# power.net
KiCad netlist of a schematic drawn in Altium Designer
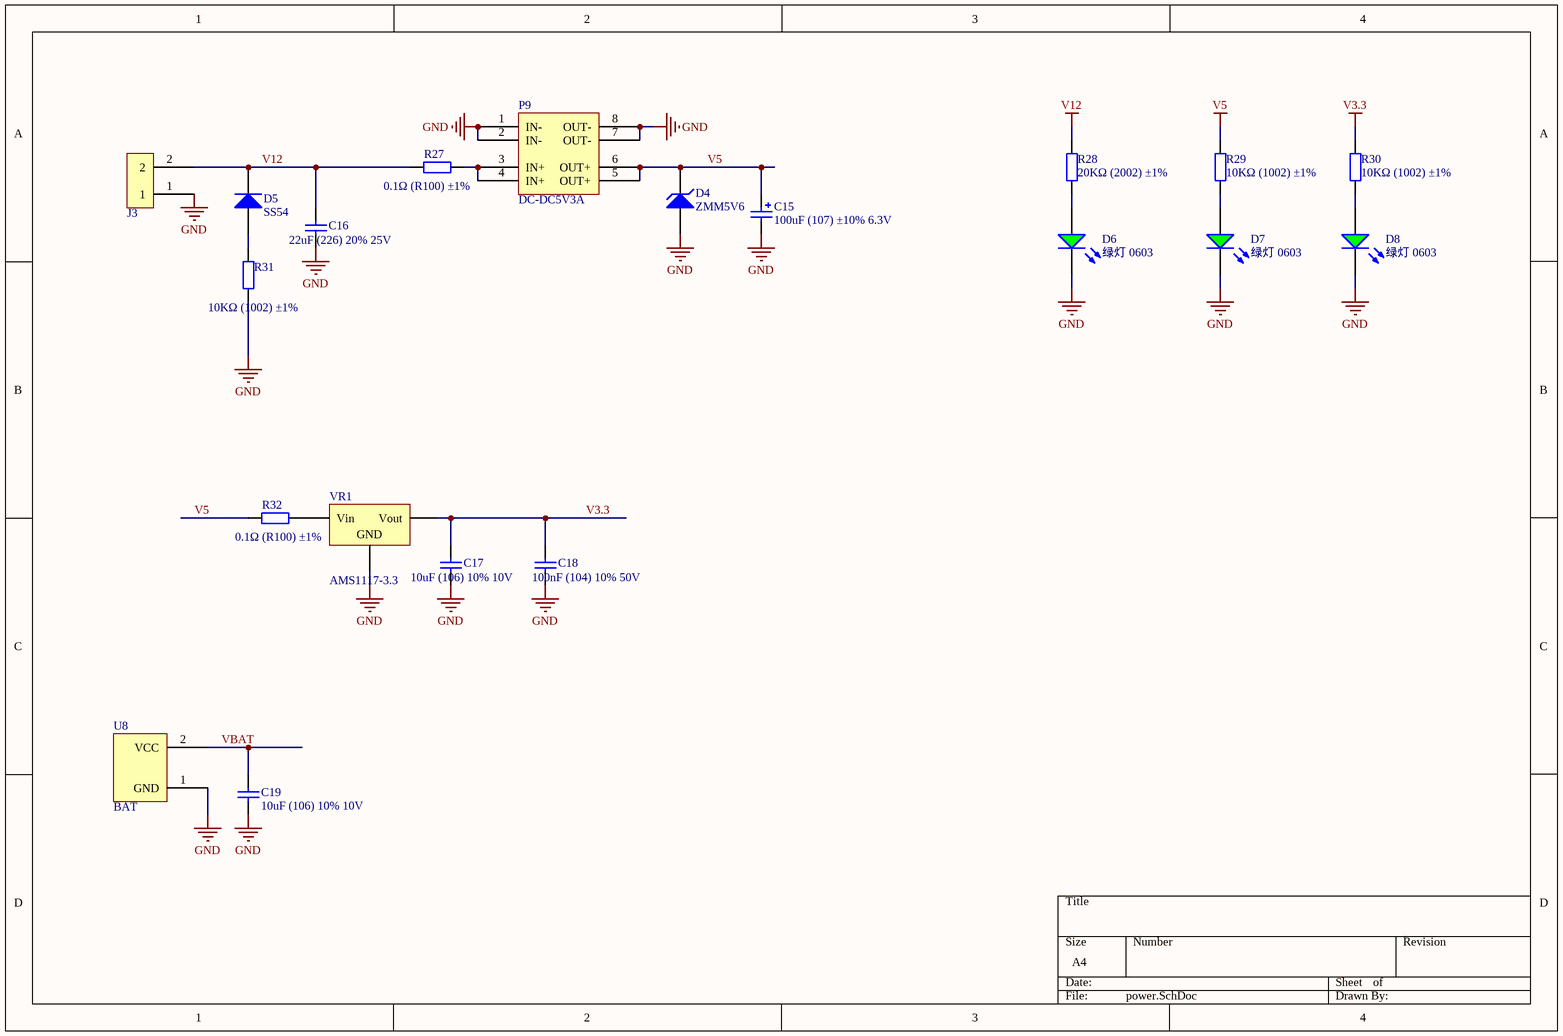
[diagram p0: power.SchDoc]

(export (version "E")
  (design (tool "Eeschema 10.0.6"))
  (components
    (comp (ref "C15")
      (value "100uF (107) ±10% 6.3V")
      (footprint "CASE-B_3528")
      (description "钽电容")
      (libsource (lib "Miscellaneous Devices LC") (part "3528 100uF (107) 10% 6.3V"))
    )
    (comp (ref "C16")
      (value "22uF (226) 20% 25V")
      (footprint "0805_C")
      (description "贴片电容")
      (libsource (lib "Miscellaneous Devices LC") (part "0805 22uF (226) 20% 25V"))
    )
    (comp (ref "C17")
      (value "10uF (106) 10% 10V")
      (footprint "0603_C")
      (description "贴片电容")
      (libsource (lib "Miscellaneous Devices LC") (part "0603 10uF (106) 10% 10V"))
    )
    (comp (ref "C18")
      (value "100nF (104) 10% 50V")
      (footprint "0603_C")
      (description "贴片电容")
      (libsource (lib "Miscellaneous Devices LC") (part "0603 100nF (104) 10% 50V"))
    )
    (comp (ref "C19")
      (value "10uF (106) 10% 10V")
      (footprint "0603_C")
      (description "贴片电容")
      (libsource (lib "Miscellaneous Devices LC") (part "0603 10uF (106) 10% 10V"))
    )
    (comp (ref "D4")
      (value "ZMM5V6")
      (footprint "LL-34")
      (description "稳压二极管")
      (libsource (lib "Miscellaneous Devices LC") (part "LL-34 ZMM5V6"))
    )
    (comp (ref "D5")
      (value "SS54")
      (footprint "SMA(DO-214AC)_S1")
      (description "二极管")
      (libsource (lib "Miscellaneous Devices LC") (part "SMA(DO-214AC) SS54"))
    )
    (comp (ref "D6")
      (value "绿灯 0603")
      (footprint "0603_LED_S1")
      (description "发光二极管")
      (libsource (lib "Miscellaneous Devices LC") (part "0603 绿灯"))
    )
    (comp (ref "D7")
      (value "绿灯 0603")
      (footprint "0603_LED_S1")
      (description "发光二极管")
      (libsource (lib "Miscellaneous Devices LC") (part "0603 绿灯"))
    )
    (comp (ref "D8")
      (value "绿灯 0603")
      (footprint "0603_LED_S1")
      (description "发光二极管")
      (libsource (lib "Miscellaneous Devices LC") (part "0603 绿灯"))
    )
    (comp (ref "J3") (value "XK7.62-2P") (footprint "XK7.62-2P") (libsource (lib "CHK-I") (part "XK7.62-2P")))
    (comp (ref "P9") (value "DC-DC5V3A") (footprint "DC-DC3A") (libsource (lib "CHK-I") (part "DC-DC3A")))
    (comp (ref "R27")
      (value "0.1Ω (R100) ±1%")
      (footprint "1206_R")
      (description "贴片电阻")
      (libsource (lib "Miscellaneous Devices LC") (part "1206 0.1Ω (R100) 1%"))
    )
    (comp (ref "R28")
      (value "20KΩ (2002) ±1%")
      (footprint "0603_R")
      (description "贴片电阻")
      (libsource (lib "Miscellaneous Devices LC") (part "0603 20KΩ (2002) 1%"))
    )
    (comp (ref "R29")
      (value "10KΩ (1002) ±1%")
      (footprint "0603_R")
      (description "贴片电阻")
      (libsource (lib "Miscellaneous Devices LC") (part "0603 10KΩ (1002) 1%"))
    )
    (comp (ref "R30")
      (value "10KΩ (1002) ±1%")
      (footprint "0603_R")
      (description "贴片电阻")
      (libsource (lib "Miscellaneous Devices LC") (part "0603 10KΩ (1002) 1%"))
    )
    (comp (ref "R31")
      (value "10KΩ (1002) ±1%")
      (footprint "0805_R")
      (description "贴片电阻")
      (libsource (lib "Miscellaneous Devices LC") (part "0805 10KΩ (1002) 1%"))
    )
    (comp (ref "R32")
      (value "0.1Ω (R100) ±1%")
      (footprint "1206_R")
      (description "贴片电阻")
      (libsource (lib "Miscellaneous Devices LC") (part "1206 0.1Ω (R100) 1%"))
    )
    (comp (ref "U8") (value "BAT") (footprint "BAT2032") (libsource (lib "CHK-I") (part "BAT2032")))
    (comp (ref "VR1")
      (value "AMS1117-3.3")
      (footprint "SOT-223")
      (description "低压差线性稳压(LDO)")
      (libsource (lib "Miscellaneous Devices LC") (part "SOT-223 AMS1117-3.3"))
    )
  )
  (nets
    (net (code "1") (name "/VBAT") (class "Default")
      (node (ref "C19") (pin "2") (pinfunction "2_2") (pintype "passive"))
      (node (ref "U8") (pin "2") (pinfunction "VCC_2") (pintype "passive"))
    )
    (net (code "2") (name "GND") (class "Default")
      (node (ref "C15") (pin "2") (pinfunction "2_2") (pintype "passive"))
      (node (ref "C16") (pin "1") (pinfunction "1_1") (pintype "passive"))
      (node (ref "C17") (pin "1") (pinfunction "1_1") (pintype "passive"))
      (node (ref "C18") (pin "1") (pinfunction "1_1") (pintype "passive"))
      (node (ref "C19") (pin "1") (pinfunction "1_1") (pintype "passive"))
      (node (ref "D4") (pin "1") (pinfunction "A_1") (pintype "passive"))
      (node (ref "D6") (pin "K") (pinfunction "K_K") (pintype "passive"))
      (node (ref "D7") (pin "K") (pinfunction "K_K") (pintype "passive"))
      (node (ref "D8") (pin "K") (pinfunction "K_K") (pintype "passive"))
      (node (ref "J3") (pin "1") (pinfunction "1_1") (pintype "passive"))
      (node (ref "P9") (pin "1") (pinfunction "IN-_1") (pintype "passive"))
      (node (ref "P9") (pin "2") (pinfunction "IN-_2") (pintype "passive"))
      (node (ref "P9") (pin "7") (pinfunction "OUT-_7") (pintype "passive"))
      (node (ref "P9") (pin "8") (pinfunction "OUT-_8") (pintype "passive"))
      (node (ref "R31") (pin "1") (pinfunction "1_1") (pintype "passive"))
      (node (ref "U8") (pin "1") (pinfunction "GND_1") (pintype "passive"))
      (node (ref "VR1") (pin "1") (pinfunction "GND_1") (pintype "passive"))
    )
    (net (code "3") (name "Net-(D5-A)") (class "Default")
      (node (ref "D5") (pin "1") (pinfunction "A_1") (pintype "passive"))
      (node (ref "R31") (pin "2") (pinfunction "2_2") (pintype "passive"))
    )
    (net (code "4") (name "Net-(D6-PadA)") (class "Default")
      (node (ref "D6") (pin "A") (pinfunction "A_A") (pintype "passive"))
      (node (ref "R28") (pin "1") (pinfunction "1_1") (pintype "passive"))
    )
    (net (code "5") (name "Net-(D7-PadA)") (class "Default")
      (node (ref "D7") (pin "A") (pinfunction "A_A") (pintype "passive"))
      (node (ref "R29") (pin "1") (pinfunction "1_1") (pintype "passive"))
    )
    (net (code "6") (name "Net-(D8-PadA)") (class "Default")
      (node (ref "D8") (pin "A") (pinfunction "A_A") (pintype "passive"))
      (node (ref "R30") (pin "1") (pinfunction "1_1") (pintype "passive"))
    )
    (net (code "7") (name "Net-(P9-IN+-Pad3)") (class "Default")
      (node (ref "P9") (pin "3") (pinfunction "IN+_3") (pintype "passive"))
      (node (ref "P9") (pin "4") (pinfunction "IN+_4") (pintype "passive"))
      (node (ref "R27") (pin "2") (pinfunction "2_2") (pintype "passive"))
    )
    (net (code "8") (name "Net-(VR1-Vin)") (class "Default")
      (node (ref "R32") (pin "2") (pinfunction "2_2") (pintype "passive"))
      (node (ref "VR1") (pin "3") (pinfunction "Vin_3") (pintype "passive"))
    )
    (net (code "9") (name "V3.3") (class "Default")
      (node (ref "C17") (pin "2") (pinfunction "2_2") (pintype "passive"))
      (node (ref "C18") (pin "2") (pinfunction "2_2") (pintype "passive"))
      (node (ref "R30") (pin "2") (pinfunction "2_2") (pintype "passive"))
      (node (ref "VR1") (pin "2") (pinfunction "Vout_2") (pintype "passive"))
    )
    (net (code "10") (name "V5") (class "Default")
      (node (ref "C15") (pin "1") (pinfunction "1_1") (pintype "passive"))
      (node (ref "D4") (pin "2") (pinfunction "K_2") (pintype "passive"))
      (node (ref "P9") (pin "5") (pinfunction "OUT+_5") (pintype "passive"))
      (node (ref "P9") (pin "6") (pinfunction "OUT+_6") (pintype "passive"))
      (node (ref "R29") (pin "2") (pinfunction "2_2") (pintype "passive"))
      (node (ref "R32") (pin "1") (pinfunction "1_1") (pintype "passive"))
    )
    (net (code "11") (name "V12") (class "Default")
      (node (ref "C16") (pin "2") (pinfunction "2_2") (pintype "passive"))
      (node (ref "D5") (pin "2") (pinfunction "K_2") (pintype "passive"))
      (node (ref "J3") (pin "2") (pinfunction "2_2") (pintype "passive"))
      (node (ref "R27") (pin "1") (pinfunction "1_1") (pintype "passive"))
      (node (ref "R28") (pin "2") (pinfunction "2_2") (pintype "passive"))
    )
  )
)
